# Xmas.net
KiCad netlist of a schematic drawn in EAGLE
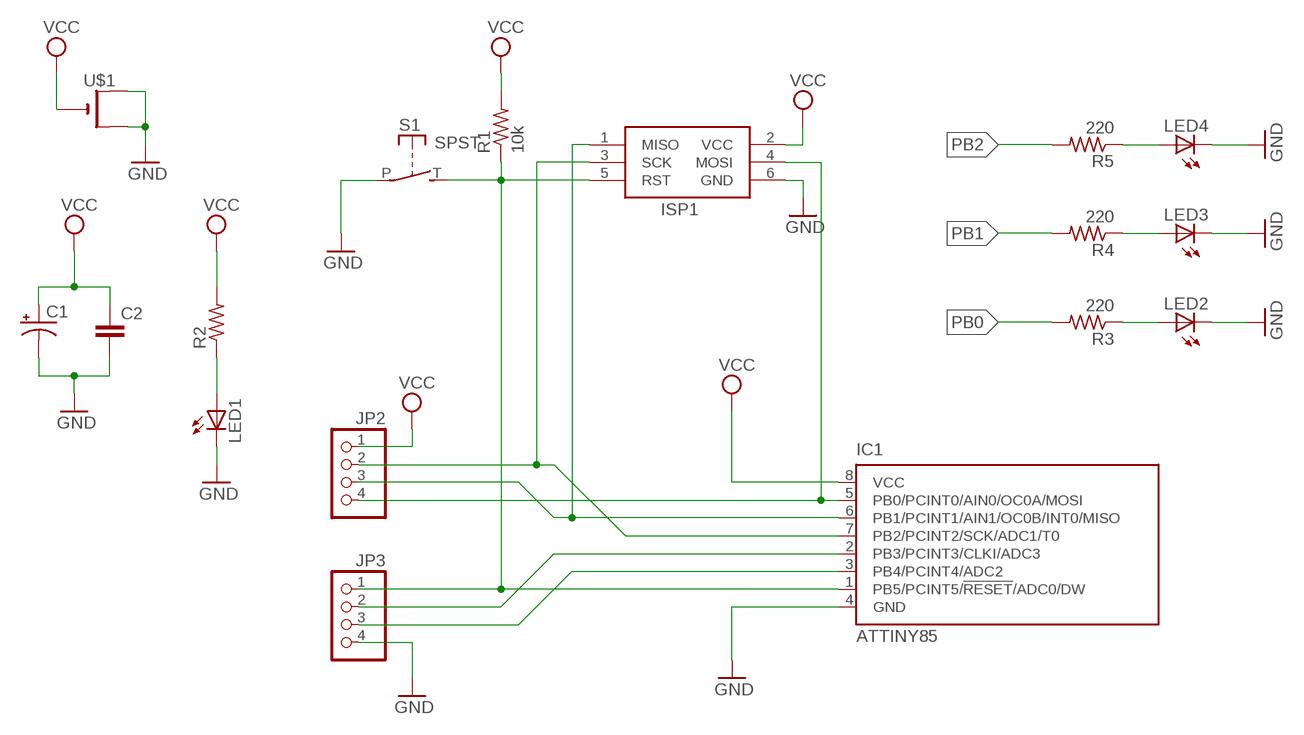
[diagram p0: schematic, sheet 1]

(export (version "E")
  (design (tool "Eeschema 10.0.6"))
  (components
    (comp (ref "C1")
      (value "100UF-25V-20%(PTH)")
      (footprint "eagle-import:CPOL-RADIAL-100UF-25V")
      (libsource (lib "eagle-import") (part "100UF-25V-20%(PTH)"))
    )
    (comp (ref "C2")
      (value "0.1UF-50V-20%(PTH)KIT-EZ")
      (footprint "eagle-import:CAP-PTH-SMALL-KIT")
      (libsource (lib "eagle-import") (part "0.1UF-50V-20%(PTH)KIT-EZ"))
    )
    (comp (ref "IC1")
      (value "ATTINY85")
      (footprint "eagle-import:DIL08")
      (fields (field (name "MPN") "ATTINY13-20PU"))
      (libsource (lib "eagle-import") (part "TINY13PU-20"))
    )
    (comp (ref "ISP1")
      (value "AVRISP-6")
      (footprint "eagle-import:AVRISP")
      (libsource (lib "eagle-import") (part "AVRISP-6"))
    )
    (comp (ref "JP2")
      (value "PINHD-1X4")
      (footprint "eagle-import:1X04")
      (libsource (lib "eagle-import") (part "PINHD-1X4"))
    )
    (comp (ref "JP3")
      (value "PINHD-1X4")
      (footprint "eagle-import:1X04")
      (libsource (lib "eagle-import") (part "PINHD-1X4"))
    )
    (comp (ref "LED1")
      (value "LED3MM")
      (footprint "eagle-import:LED3MM")
      (libsource (lib "eagle-import") (part "LED3MM"))
    )
    (comp (ref "LED2")
      (value "LED3MM")
      (footprint "eagle-import:LED3MM")
      (libsource (lib "eagle-import") (part "LED3MM"))
    )
    (comp (ref "LED3")
      (value "LED3MM")
      (footprint "eagle-import:LED3MM")
      (libsource (lib "eagle-import") (part "LED3MM"))
    )
    (comp (ref "LED4")
      (value "LED3MM")
      (footprint "eagle-import:LED3MM")
      (libsource (lib "eagle-import") (part "LED3MM"))
    )
    (comp (ref "R1")
      (value "10k")
      (footprint "eagle-import:0207_9")
      (libsource (lib "eagle-import") (part "R-US_0207/9"))
    )
    (comp (ref "R2")
      (value "R-US_0207/9")
      (footprint "eagle-import:0207_9")
      (libsource (lib "eagle-import") (part "R-US_0207/9"))
    )
    (comp (ref "R3")
      (value "220")
      (footprint "eagle-import:0207_9")
      (libsource (lib "eagle-import") (part "R-US_0207/9"))
    )
    (comp (ref "R4")
      (value "220")
      (footprint "eagle-import:0207_9")
      (libsource (lib "eagle-import") (part "R-US_0207/9"))
    )
    (comp (ref "R5")
      (value "220")
      (footprint "eagle-import:0207_9")
      (libsource (lib "eagle-import") (part "R-US_0207/9"))
    )
    (comp (ref "S1")
      (value "SPST")
      (footprint "eagle-import:JUDCOSPST")
      (libsource (lib "eagle-import") (part "SPST"))
    )
    (comp (ref "U$1")
      (value "CR1220THM")
      (footprint "eagle-import:CR1220-THM")
      (libsource (lib "eagle-import") (part "CR1220THM"))
    )
  )
  (nets
    (net (code "1") (name "GND") (class "Default")
      (node (ref "C1") (pin "2") (pinfunction "-_2") (pintype "passive"))
      (node (ref "C2") (pin "2") (pinfunction "2_2") (pintype "passive"))
      (node (ref "IC1") (pin "4") (pinfunction "GND_4") (pintype "power_in"))
      (node (ref "ISP1") (pin "6") (pinfunction "GND_6") (pintype "power_in"))
      (node (ref "JP3") (pin "4") (pinfunction "4_4") (pintype "passive"))
      (node (ref "LED1") (pin "K") (pinfunction "C_K") (pintype "passive"))
      (node (ref "LED2") (pin "K") (pinfunction "C_K") (pintype "passive"))
      (node (ref "LED3") (pin "K") (pinfunction "C_K") (pintype "passive"))
      (node (ref "LED4") (pin "K") (pinfunction "C_K") (pintype "passive"))
      (node (ref "S1") (pin "P") (pinfunction "P_P") (pintype "passive"))
      (node (ref "U$1") (pin "+1") (pinfunction "+_+1") (pintype "passive"))
      (node (ref "U$1") (pin "+2") (pinfunction "+1_+2") (pintype "passive"))
    )
    (net (code "2") (name "Net-(IC1-PB3{slash}PCINT3{slash}CLKI{slash}ADC3)") (class "Default")
      (node (ref "IC1") (pin "2") (pinfunction "PB3/PCINT3/CLKI/ADC3_2") (pintype "bidirectional"))
      (node (ref "JP3") (pin "2") (pinfunction "2_2") (pintype "passive"))
    )
    (net (code "3") (name "Net-(IC1-PB4{slash}PCINT4{slash}ADC2)") (class "Default")
      (node (ref "IC1") (pin "3") (pinfunction "PB4/PCINT4/ADC2_3") (pintype "bidirectional"))
      (node (ref "JP3") (pin "3") (pinfunction "3_3") (pintype "passive"))
    )
    (net (code "4") (name "Net-(IC1-PB5{slash}PCINT5{slash}~{RESET}{slash}ADC0{slash}DW)") (class "Default")
      (node (ref "IC1") (pin "1") (pinfunction "PB5/PCINT5/~{RESET}/ADC0/DW_1") (pintype "bidirectional"))
      (node (ref "ISP1") (pin "5") (pinfunction "RST_5") (pintype "output"))
      (node (ref "JP3") (pin "1") (pinfunction "1_1") (pintype "passive"))
      (node (ref "R1") (pin "1") (pinfunction "1_1") (pintype "passive"))
      (node (ref "S1") (pin "T") (pinfunction "S_T") (pintype "passive"))
    )
    (net (code "5") (name "Net-(LED1-PadA)") (class "Default")
      (node (ref "LED1") (pin "A") (pinfunction "A_A") (pintype "passive"))
      (node (ref "R2") (pin "1") (pinfunction "1_1") (pintype "passive"))
    )
    (net (code "6") (name "Net-(LED2-PadA)") (class "Default")
      (node (ref "LED2") (pin "A") (pinfunction "A_A") (pintype "passive"))
      (node (ref "R3") (pin "1") (pinfunction "1_1") (pintype "passive"))
    )
    (net (code "7") (name "Net-(LED3-PadA)") (class "Default")
      (node (ref "LED3") (pin "A") (pinfunction "A_A") (pintype "passive"))
      (node (ref "R4") (pin "1") (pinfunction "1_1") (pintype "passive"))
    )
    (net (code "8") (name "Net-(LED4-PadA)") (class "Default")
      (node (ref "LED4") (pin "A") (pinfunction "A_A") (pintype "passive"))
      (node (ref "R5") (pin "1") (pinfunction "1_1") (pintype "passive"))
    )
    (net (code "9") (name "PB0") (class "Default")
      (node (ref "IC1") (pin "5") (pinfunction "PB0/PCINT0/AIN0/OC0A/MOSI_5") (pintype "bidirectional"))
      (node (ref "ISP1") (pin "4") (pinfunction "MOSI_4") (pintype "output"))
      (node (ref "JP2") (pin "4") (pinfunction "4_4") (pintype "passive"))
      (node (ref "R3") (pin "2") (pinfunction "2_2") (pintype "passive"))
    )
    (net (code "10") (name "PB1") (class "Default")
      (node (ref "IC1") (pin "6") (pinfunction "PB1/PCINT1/AIN1/OC0B/INT0/MISO_6") (pintype "bidirectional"))
      (node (ref "ISP1") (pin "1") (pinfunction "MISO_1") (pintype "input"))
      (node (ref "JP2") (pin "3") (pinfunction "3_3") (pintype "passive"))
      (node (ref "R4") (pin "2") (pinfunction "2_2") (pintype "passive"))
    )
    (net (code "11") (name "PB2") (class "Default")
      (node (ref "IC1") (pin "7") (pinfunction "PB2/PCINT2/SCK/ADC1/T0_7") (pintype "bidirectional"))
      (node (ref "ISP1") (pin "3") (pinfunction "SCK_3") (pintype "output"))
      (node (ref "JP2") (pin "2") (pinfunction "2_2") (pintype "passive"))
      (node (ref "R5") (pin "2") (pinfunction "2_2") (pintype "passive"))
    )
    (net (code "12") (name "VCC") (class "Default")
      (node (ref "C1") (pin "1") (pinfunction "+_1") (pintype "passive"))
      (node (ref "C2") (pin "1") (pinfunction "1_1") (pintype "passive"))
      (node (ref "IC1") (pin "8") (pinfunction "VCC_8") (pintype "power_in"))
      (node (ref "ISP1") (pin "2") (pinfunction "VCC_2") (pintype "power_in"))
      (node (ref "JP2") (pin "1") (pinfunction "1_1") (pintype "passive"))
      (node (ref "R1") (pin "2") (pinfunction "2_2") (pintype "passive"))
      (node (ref "R2") (pin "2") (pinfunction "2_2") (pintype "passive"))
      (node (ref "U$1") (pin "-") (pinfunction "-_-") (pintype "passive"))
    )
  )
)
